# iridia-tam-left-board.net
KiCad netlist of a schematic drawn in EAGLE
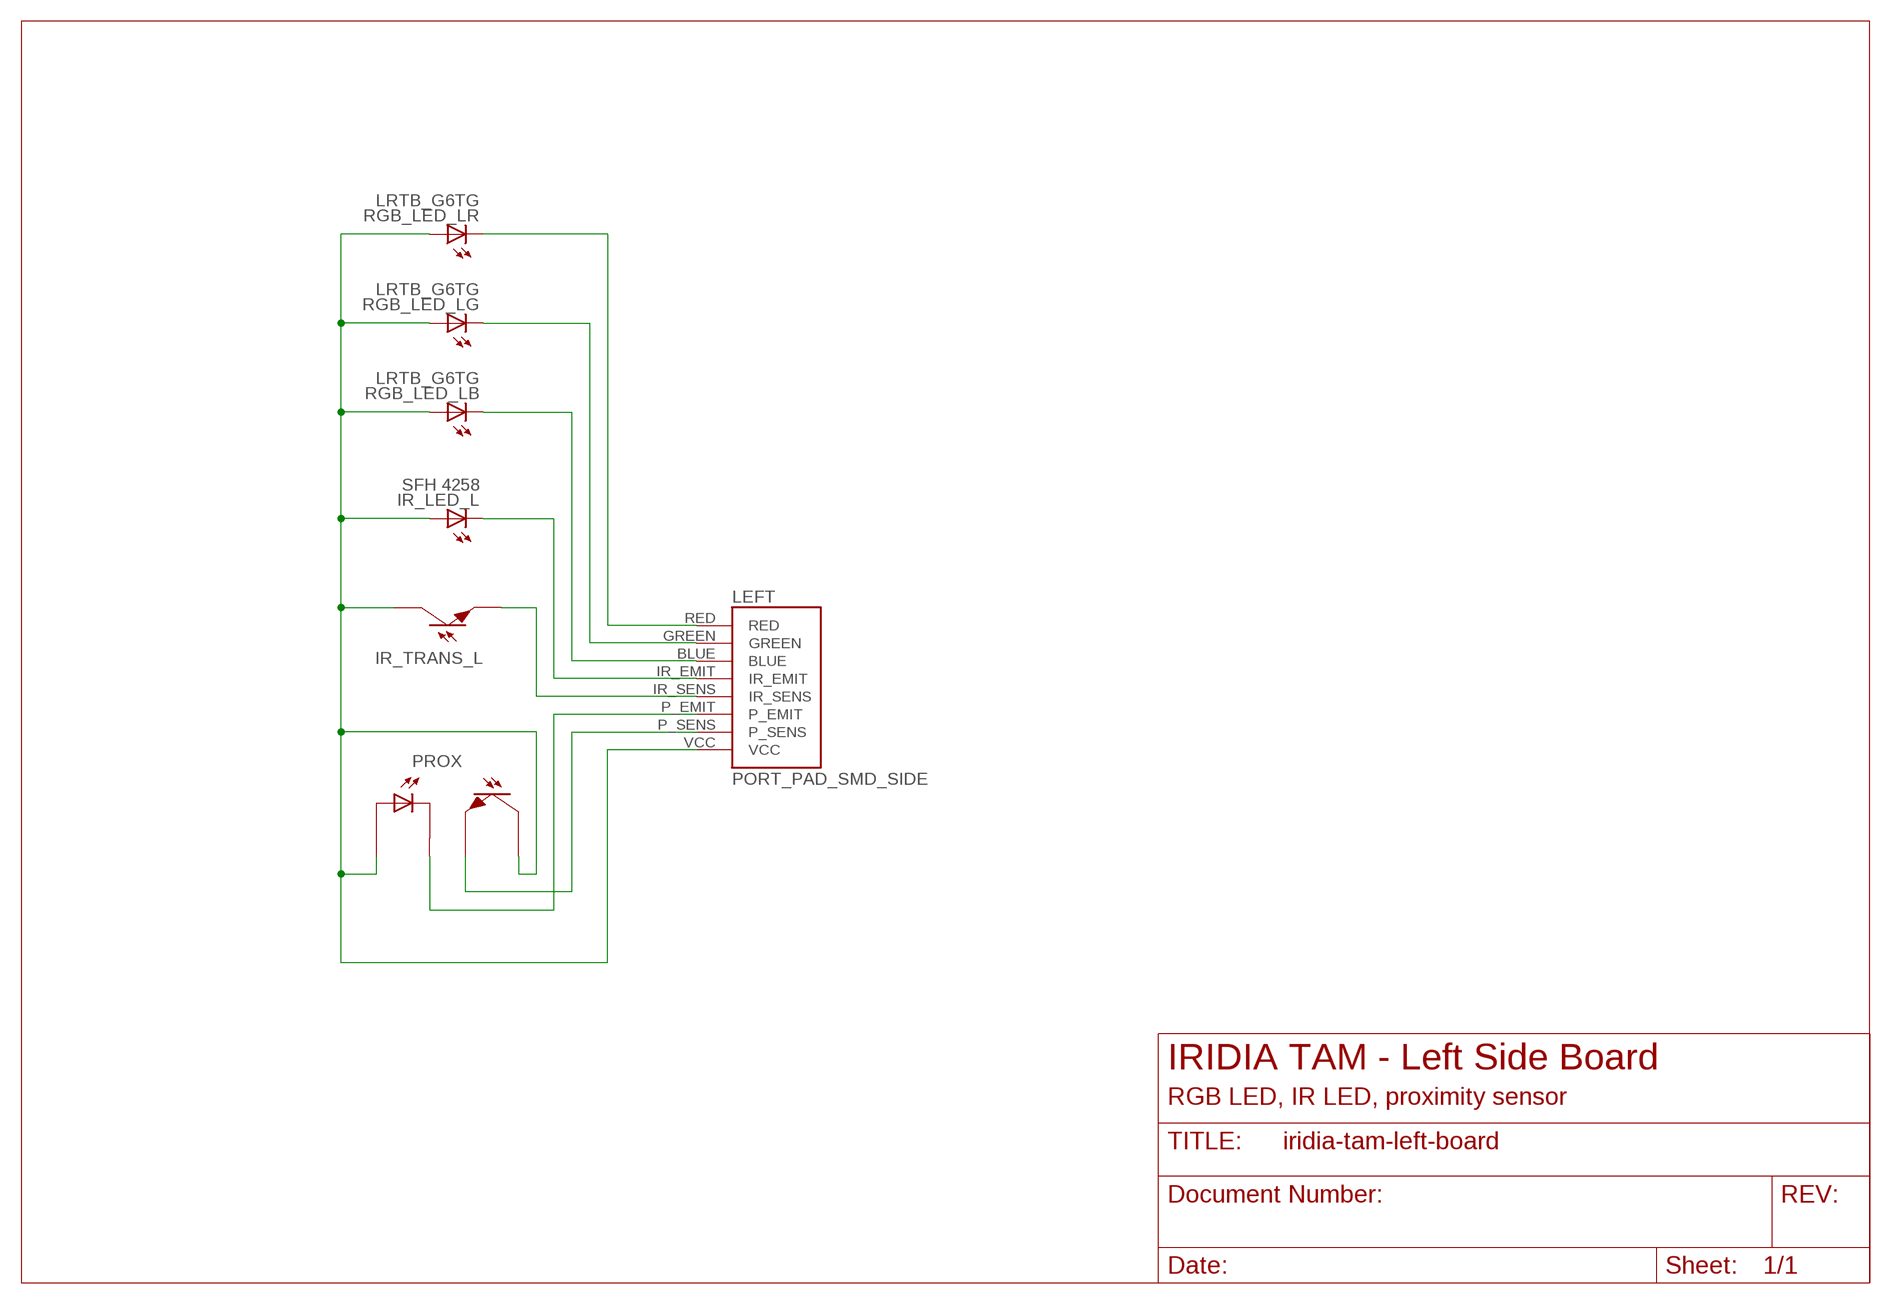
[diagram p0: schematic, sheet 1]

(export (version "E")
  (design (tool "Eeschema 10.0.6"))
  (components
    (comp (ref "IR_LED_L")
      (value "SFH 4258")
      (footprint "eagle-import:P-LCC-4-1C-3A")
      (libsource (lib "eagle-import") (part "LEDP-LCC-4"))
    )
    (comp (ref "IR_TRANS_L")
      (value "SFH 320 FA")
      (footprint "eagle-import:P-LCC-2-TRANS")
      (libsource (lib "eagle-import") (part "IR_TRANSP-LCC-2"))
    )
    (comp (ref "LEFT")
      (value "PORT_PAD_SMD_SIDE")
      (footprint "eagle-import:PORT_PAD_SMD_SIDE")
      (libsource (lib "eagle-import") (part "PORT_PAD_SMD_SIDE"))
    )
    (comp (ref "PROX")
      (value "TCRT1000")
      (footprint "eagle-import:TCRT1000_TH")
      (libsource (lib "eagle-import") (part "TCRT1000_TH"))
    )
    (comp (ref "RGB_LED_L")
      (value "LRTB_G6TG")
      (footprint "eagle-import:P-LCC-6_TOPLED")
      (libsource (lib "eagle-import") (part "MULTILED_LRTB_G6TG"))
    )
  )
  (nets
    (net (code "1") (name "Net-(IR_LED_L-C)") (class "Default")
      (node (ref "IR_LED_L") (pin "C@1") (pinfunction "C_C@1") (pintype "passive"))
      (node (ref "LEFT") (pin "IR_EMIT") (pinfunction "IR_EMIT_IR_EMIT") (pintype "bidirectional"))
    )
    (net (code "2") (name "Net-(IR_TRANS_L-PadE)") (class "Default")
      (node (ref "IR_TRANS_L") (pin "E") (pinfunction "E_E") (pintype "passive"))
      (node (ref "LEFT") (pin "IR_SENS") (pinfunction "IR_SENS_IR_SENS") (pintype "bidirectional"))
    )
    (net (code "3") (name "Net-(LEFT-PadP_EMIT)") (class "Default")
      (node (ref "LEFT") (pin "P_EMIT") (pinfunction "P_EMIT_P_EMIT") (pintype "bidirectional"))
      (node (ref "PROX") (pin "CAT") (pinfunction "CAT_CAT") (pintype "passive"))
    )
    (net (code "4") (name "Net-(LEFT-PadP_SENS)") (class "Default")
      (node (ref "LEFT") (pin "P_SENS") (pinfunction "P_SENS_P_SENS") (pintype "bidirectional"))
      (node (ref "PROX") (pin "E") (pinfunction "E_E") (pintype "passive"))
    )
    (net (code "5") (name "Net-(RGB_LED_LA-A)") (class "Default")
      (node (ref "IR_LED_L") (pin "A@2") (pinfunction "A_A@2") (pintype "passive"))
      (node (ref "IR_LED_L") (pin "A@3") (pinfunction "A_A@3") (pintype "passive"))
      (node (ref "IR_LED_L") (pin "A@4") (pinfunction "A_A@4") (pintype "passive"))
      (node (ref "IR_TRANS_L") (pin "COL") (pinfunction "COL_COL") (pintype "passive"))
      (node (ref "LEFT") (pin "VCC") (pinfunction "VCC_VCC") (pintype "bidirectional"))
      (node (ref "PROX") (pin "A") (pinfunction "A_A") (pintype "passive"))
      (node (ref "PROX") (pin "COL") (pinfunction "COL_COL") (pintype "passive"))
      (node (ref "RGB_LED_L") (pin "A1") (pinfunction "A_A1") (pintype "passive"))
      (node (ref "RGB_LED_L") (pin "A2") (pinfunction "A_A2") (pintype "passive"))
      (node (ref "RGB_LED_L") (pin "A3") (pinfunction "A_A3") (pintype "passive"))
    )
    (net (code "6") (name "Net-(RGB_LED_LA-C)") (class "Default")
      (node (ref "LEFT") (pin "BLUE") (pinfunction "BLUE_BLUE") (pintype "bidirectional"))
      (node (ref "RGB_LED_L") (pin "C3") (pinfunction "C_C3") (pintype "passive"))
    )
    (net (code "7") (name "Net-(RGB_LED_LB-C)") (class "Default")
      (node (ref "LEFT") (pin "GREEN") (pinfunction "GREEN_GREEN") (pintype "bidirectional"))
      (node (ref "RGB_LED_L") (pin "C2") (pinfunction "C_C2") (pintype "passive"))
    )
    (net (code "8") (name "Net-(RGB_LED_LC-C)") (class "Default")
      (node (ref "LEFT") (pin "RED") (pinfunction "RED_RED") (pintype "bidirectional"))
      (node (ref "RGB_LED_L") (pin "C1") (pinfunction "C_C1") (pintype "passive"))
    )
  )
)
